# RasPiTimePowerSWv_1_5.net
KiCad netlist of a schematic drawn in EAGLE
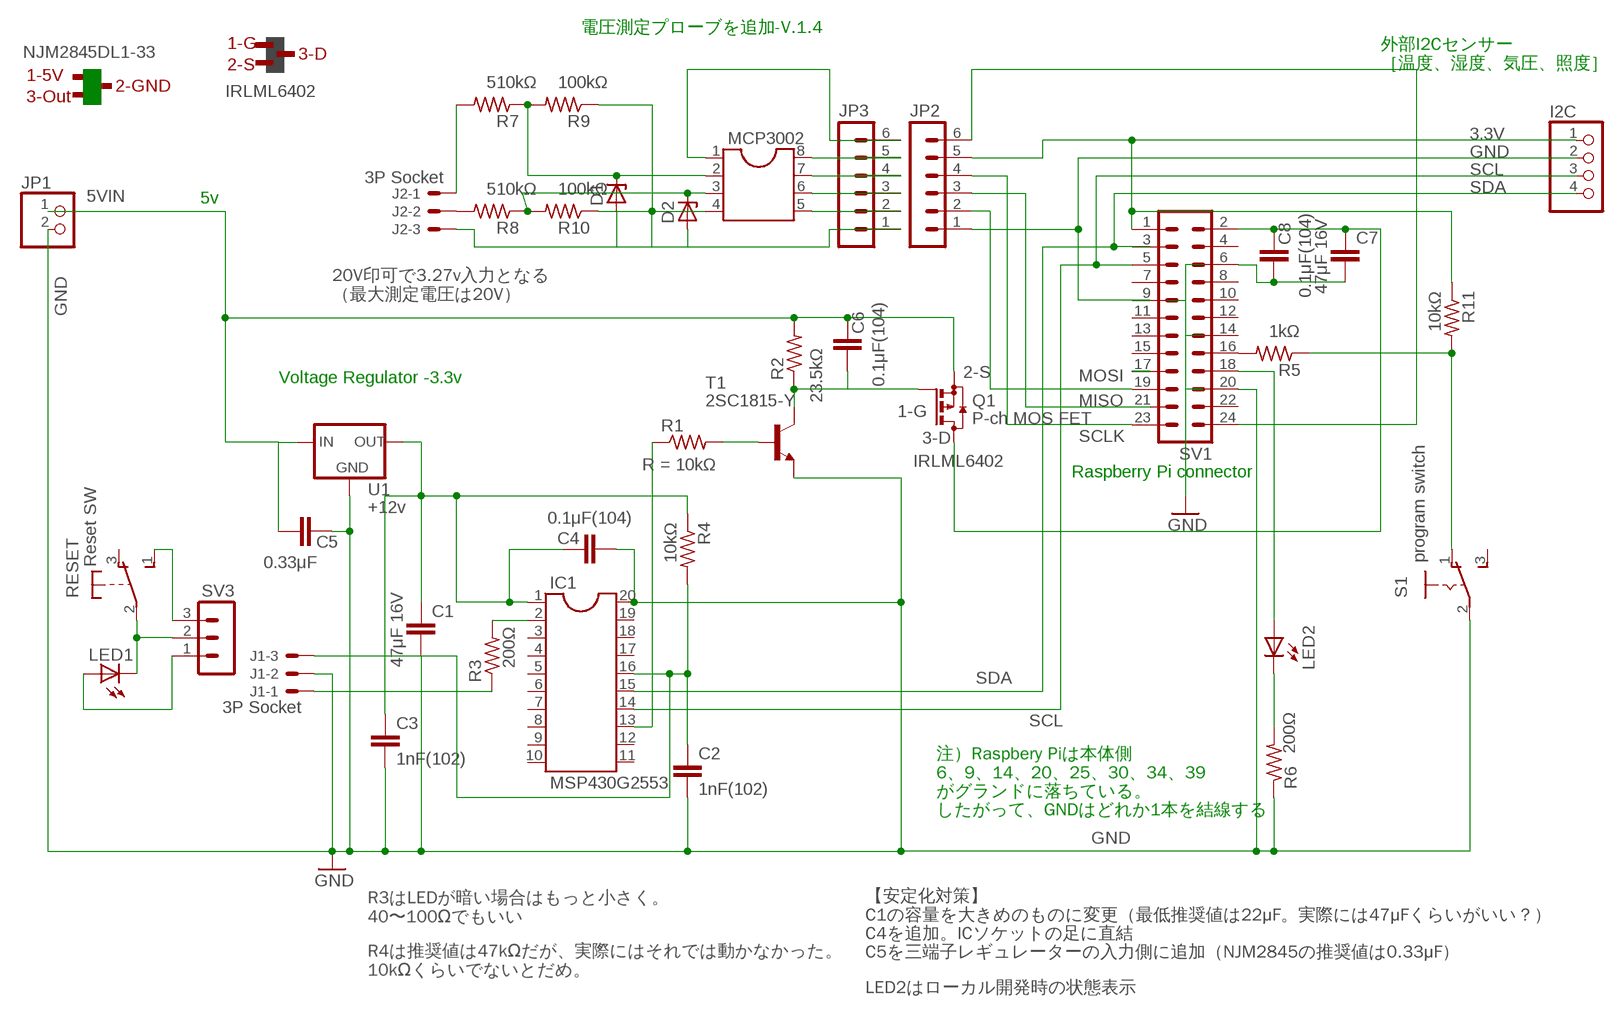
[diagram p0: schematic, sheet 1]

(export (version "E")
  (design (tool "Eeschema 10.0.6"))
  (components
    (comp (ref "C1")
      (value "47μF 16V")
      (footprint "eagle-import:C075-042X103")
      (libsource (lib "eagle-import") (part "C-EU075-042X103"))
    )
    (comp (ref "C2")
      (value "1nF(102)")
      (footprint "eagle-import:C025-024X044")
      (libsource (lib "eagle-import") (part "C-EU025-024X044"))
    )
    (comp (ref "C3")
      (value "1nF(102)")
      (footprint "eagle-import:C025-024X044")
      (libsource (lib "eagle-import") (part "C-EU025-024X044"))
    )
    (comp (ref "C4")
      (value "0.1μF(104)")
      (footprint "eagle-import:C025-024X044")
      (libsource (lib "eagle-import") (part "C-EU025-024X044"))
    )
    (comp (ref "C5")
      (value "0.33μF")
      (footprint "eagle-import:C025-024X044")
      (libsource (lib "eagle-import") (part "C-EU025-024X044"))
    )
    (comp (ref "C6")
      (value "0.1μF(104)")
      (footprint "eagle-import:C025-024X044")
      (libsource (lib "eagle-import") (part "C-EU025-024X044"))
    )
    (comp (ref "C7")
      (value "47μF 16V")
      (footprint "eagle-import:C075-042X103")
      (libsource (lib "eagle-import") (part "C-EU075-042X103"))
    )
    (comp (ref "C8")
      (value "0.1μF(104)")
      (footprint "eagle-import:C025-024X044")
      (libsource (lib "eagle-import") (part "C-EU025-024X044"))
    )
    (comp (ref "D1")
      (value "ZENER-DIODEDO34-7")
      (footprint "eagle-import:DO34Z7")
      (libsource (lib "eagle-import") (part "ZENER-DIODEDO34-7"))
    )
    (comp (ref "D2")
      (value "ZENER-DIODEDO34-7")
      (footprint "eagle-import:DO34Z7")
      (libsource (lib "eagle-import") (part "ZENER-DIODEDO34-7"))
    )
    (comp (ref "I2C")
      (value "PINHD-1X4")
      (footprint "eagle-import:1X04")
      (libsource (lib "eagle-import") (part "PINHD-1X4"))
    )
    (comp (ref "IC1")
      (value "MSP430G2553")
      (footprint "eagle-import:SOCKET-20")
      (libsource (lib "eagle-import") (part "DIL20S"))
    )
    (comp (ref "J1")
      (value "3P Socket")
      (footprint "eagle-import:6410-03")
      (libsource (lib "eagle-import") (part "22-?-0327-2031"))
    )
    (comp (ref "J2")
      (value "3P Socket")
      (footprint "eagle-import:6410-03")
      (libsource (lib "eagle-import") (part "22-?-0327-2031"))
    )
    (comp (ref "JP1")
      (value "PINHD-1X2")
      (footprint "eagle-import:1X02")
      (libsource (lib "eagle-import") (part "PINHD-1X2"))
    )
    (comp (ref "JP2")
      (value "MA06-1")
      (footprint "eagle-import:MA06-1")
      (libsource (lib "eagle-import") (part "MA06-1"))
    )
    (comp (ref "JP3")
      (value "MA06-1")
      (footprint "eagle-import:MA06-1")
      (libsource (lib "eagle-import") (part "MA06-1"))
    )
    (comp (ref "LED1")
      (value "TLLG4400")
      (footprint "eagle-import:LED3MM")
      (fields (field (name "MF") "VISHAY SEMICONDUCTOR"))
      (libsource (lib "eagle-import") (part "TLLG4400"))
    )
    (comp (ref "LED2")
      (value "TLLG4400")
      (footprint "eagle-import:LED3MM")
      (fields (field (name "MF") "VISHAY SEMICONDUCTOR"))
      (libsource (lib "eagle-import") (part "TLLG4400"))
    )
    (comp (ref "MCP3002")
      (value "DIL8")
      (footprint "eagle-import:DIL08")
      (libsource (lib "eagle-import") (part "DIL8"))
    )
    (comp (ref "Q1")
      (value "P-ch MOS FET")
      (footprint "eagle-import:SOT23")
      (libsource (lib "eagle-import") (part "BSS84"))
    )
    (comp (ref "R1")
      (value "R-US_MELF0102W")
      (footprint "eagle-import:MINI_MELF-0102W")
      (fields (field (name "R") "10kΩ"))
      (libsource (lib "eagle-import") (part "R-US_MELF0102W"))
    )
    (comp (ref "R2")
      (value "R-US_MELF0102W")
      (footprint "eagle-import:MINI_MELF-0102W")
      (fields (field (name "1K") "23.5kΩ"))
      (libsource (lib "eagle-import") (part "R-US_MELF0102W"))
    )
    (comp (ref "R3")
      (value "R-US_MELF0102W")
      (footprint "eagle-import:MINI_MELF-0102W")
      (fields (field (name "R") "200Ω"))
      (libsource (lib "eagle-import") (part "R-US_MELF0102W"))
    )
    (comp (ref "R4")
      (value "10kΩ")
      (footprint "eagle-import:MINI_MELF-0102W")
      (libsource (lib "eagle-import") (part "R-US_MELF0102W"))
    )
    (comp (ref "R5")
      (value "R-US_MELF0102W")
      (footprint "eagle-import:MINI_MELF-0102W")
      (fields (field (name "1K") "1kΩ"))
      (libsource (lib "eagle-import") (part "R-US_MELF0102W"))
    )
    (comp (ref "R6")
      (value "R-US_MELF0102W")
      (footprint "eagle-import:MINI_MELF-0102W")
      (fields (field (name "R") "200Ω"))
      (libsource (lib "eagle-import") (part "R-US_MELF0102W"))
    )
    (comp (ref "R7")
      (value "R-US_MELF0102W")
      (footprint "eagle-import:MINI_MELF-0102W")
      (fields (field (name "1K") "510kΩ"))
      (libsource (lib "eagle-import") (part "R-US_MELF0102W"))
    )
    (comp (ref "R8")
      (value "R-US_MELF0102W")
      (footprint "eagle-import:MINI_MELF-0102W")
      (fields (field (name "1K") "510kΩ"))
      (libsource (lib "eagle-import") (part "R-US_MELF0102W"))
    )
    (comp (ref "R9")
      (value "R-US_MELF0102W")
      (footprint "eagle-import:MINI_MELF-0102W")
      (fields (field (name "1K") "100kΩ"))
      (libsource (lib "eagle-import") (part "R-US_MELF0102W"))
    )
    (comp (ref "R10")
      (value "R-US_MELF0102W")
      (footprint "eagle-import:MINI_MELF-0102W")
      (fields (field (name "1K") "100kΩ"))
      (libsource (lib "eagle-import") (part "R-US_MELF0102W"))
    )
    (comp (ref "R11")
      (value "10kΩ")
      (footprint "eagle-import:MINI_MELF-0102W")
      (libsource (lib "eagle-import") (part "R-US_MELF0102W"))
    )
    (comp (ref "RESET")
      (value "Reset SW")
      (footprint "eagle-import:9450-1")
      (libsource (lib "eagle-import") (part "9450-1"))
    )
    (comp (ref "S1")
      (value "program switch")
      (footprint "eagle-import:255SB")
      (libsource (lib "eagle-import") (part "255SB"))
    )
    (comp (ref "SV1")
      (value "MA12-2")
      (footprint "eagle-import:MA12-2")
      (libsource (lib "eagle-import") (part "MA12-2"))
    )
    (comp (ref "SV3")
      (value "MA03-1")
      (footprint "eagle-import:MA03-1")
      (libsource (lib "eagle-import") (part "MA03-1"))
    )
    (comp (ref "T1")
      (value "2SC1815-Y")
      (footprint "eagle-import:TO92-ECB")
      (libsource (lib "eagle-import") (part "2SC1815"))
    )
    (comp (ref "U1")
      (value "+12v")
      (footprint "eagle-import:TO-252")
      (libsource (lib "eagle-import") (part "V_REG_78XX7812"))
    )
  )
  (nets
    (net (code "1") (name "/3.3V") (class "Default")
      (node (ref "C1") (pin "1") (pinfunction "1_1") (pintype "passive"))
      (node (ref "C3") (pin "1") (pinfunction "1_1") (pintype "passive"))
      (node (ref "C4") (pin "1") (pinfunction "1_1") (pintype "passive"))
      (node (ref "I2C") (pin "1") (pinfunction "1_1") (pintype "passive"))
      (node (ref "IC1") (pin "1") (pinfunction "1_1") (pintype "passive"))
      (node (ref "JP2") (pin "5") (pinfunction "5_5") (pintype "passive"))
      (node (ref "R11") (pin "1") (pinfunction "1_1") (pintype "passive"))
      (node (ref "R4") (pin "1") (pinfunction "1_1") (pintype "passive"))
      (node (ref "SV1") (pin "1") (pinfunction "1_1") (pintype "passive"))
      (node (ref "U1") (pin "2") (pinfunction "OUT_2") (pintype "passive"))
    )
    (net (code "2") (name "/5VIN") (class "Default")
      (node (ref "C5") (pin "2") (pinfunction "2_2") (pintype "passive"))
      (node (ref "C6") (pin "1") (pinfunction "1_1") (pintype "passive"))
      (node (ref "JP1") (pin "1") (pinfunction "1_1") (pintype "passive"))
      (node (ref "Q1") (pin "2") (pinfunction "S_2") (pintype "passive"))
      (node (ref "R2") (pin "2") (pinfunction "2_2") (pintype "passive"))
      (node (ref "U1") (pin "1") (pinfunction "IN_1") (pintype "input"))
    )
    (net (code "3") (name "/MISO") (class "Default")
      (node (ref "JP2") (pin "3") (pinfunction "3_3") (pintype "passive"))
      (node (ref "SV1") (pin "21") (pinfunction "21_21") (pintype "passive"))
    )
    (net (code "4") (name "/MOSI") (class "Default")
      (node (ref "JP2") (pin "2") (pinfunction "2_2") (pintype "passive"))
      (node (ref "SV1") (pin "19") (pinfunction "19_19") (pintype "passive"))
    )
    (net (code "5") (name "/SCL") (class "Default")
      (node (ref "I2C") (pin "3") (pinfunction "3_3") (pintype "passive"))
      (node (ref "IC1") (pin "14") (pinfunction "14_14") (pintype "passive"))
      (node (ref "SV1") (pin "5") (pinfunction "5_5") (pintype "passive"))
    )
    (net (code "6") (name "/SCLK") (class "Default")
      (node (ref "JP2") (pin "4") (pinfunction "4_4") (pintype "passive"))
      (node (ref "SV1") (pin "23") (pinfunction "23_23") (pintype "passive"))
    )
    (net (code "7") (name "/SDA") (class "Default")
      (node (ref "I2C") (pin "4") (pinfunction "4_4") (pintype "passive"))
      (node (ref "IC1") (pin "15") (pinfunction "15_15") (pintype "passive"))
      (node (ref "SV1") (pin "3") (pinfunction "3_3") (pintype "passive"))
    )
    (net (code "8") (name "GND") (class "Default")
      (node (ref "C1") (pin "2") (pinfunction "2_2") (pintype "passive"))
      (node (ref "C2") (pin "2") (pinfunction "2_2") (pintype "passive"))
      (node (ref "C3") (pin "2") (pinfunction "2_2") (pintype "passive"))
      (node (ref "C4") (pin "2") (pinfunction "2_2") (pintype "passive"))
      (node (ref "C5") (pin "1") (pinfunction "1_1") (pintype "passive"))
      (node (ref "I2C") (pin "2") (pinfunction "2_2") (pintype "passive"))
      (node (ref "IC1") (pin "20") (pinfunction "20_20") (pintype "passive"))
      (node (ref "J1") (pin "2") (pinfunction "S_2") (pintype "passive"))
      (node (ref "JP1") (pin "2") (pinfunction "2_2") (pintype "passive"))
      (node (ref "JP2") (pin "1") (pinfunction "1_1") (pintype "passive"))
      (node (ref "R6") (pin "1") (pinfunction "1_1") (pintype "passive"))
      (node (ref "S1") (pin "2") (pinfunction "P_2") (pintype "passive"))
      (node (ref "SV1") (pin "20") (pinfunction "20_20") (pintype "passive"))
      (node (ref "SV1") (pin "9") (pinfunction "9_9") (pintype "passive"))
      (node (ref "T1") (pin "E") (pinfunction "E_E") (pintype "passive"))
      (node (ref "U1") (pin "3") (pinfunction "GND_3") (pintype "input"))
    )
    (net (code "9") (name "Net-(C7-Pad2)") (class "Default")
      (node (ref "C7") (pin "2") (pinfunction "2_2") (pintype "passive"))
      (node (ref "C8") (pin "2") (pinfunction "2_2") (pintype "passive"))
      (node (ref "SV1") (pin "6") (pinfunction "6_6") (pintype "passive"))
    )
    (net (code "10") (name "Net-(D1-PadC)") (class "Default")
      (node (ref "D1") (pin "C") (pinfunction "C_C") (pintype "passive"))
      (node (ref "MCP3002") (pin "2") (pinfunction "2_2") (pintype "passive"))
      (node (ref "R7") (pin "1") (pinfunction "1_1") (pintype "passive"))
      (node (ref "R9") (pin "2") (pinfunction "2_2") (pintype "passive"))
    )
    (net (code "11") (name "Net-(D2-PadC)") (class "Default")
      (node (ref "D2") (pin "C") (pinfunction "C_C") (pintype "passive"))
      (node (ref "MCP3002") (pin "3") (pinfunction "3_3") (pintype "passive"))
      (node (ref "R10") (pin "2") (pinfunction "2_2") (pintype "passive"))
      (node (ref "R8") (pin "1") (pinfunction "1_1") (pintype "passive"))
    )
    (net (code "12") (name "Net-(IC1-Pad2)") (class "Default")
      (node (ref "IC1") (pin "2") (pinfunction "2_2") (pintype "passive"))
      (node (ref "R3") (pin "2") (pinfunction "2_2") (pintype "passive"))
    )
    (net (code "13") (name "Net-(IC1-Pad13)") (class "Default")
      (node (ref "IC1") (pin "13") (pinfunction "13_13") (pintype "passive"))
      (node (ref "R1") (pin "1") (pinfunction "1_1") (pintype "passive"))
    )
    (net (code "14") (name "Net-(J1A-S)") (class "Default")
      (node (ref "J1") (pin "1") (pinfunction "S_1") (pintype "passive"))
      (node (ref "R3") (pin "1") (pinfunction "1_1") (pintype "passive"))
    )
    (net (code "15") (name "Net-(J1C-S)") (class "Default")
      (node (ref "C2") (pin "1") (pinfunction "1_1") (pintype "passive"))
      (node (ref "IC1") (pin "16") (pinfunction "16_16") (pintype "passive"))
      (node (ref "J1") (pin "3") (pinfunction "S_3") (pintype "passive"))
      (node (ref "R4") (pin "2") (pinfunction "2_2") (pintype "passive"))
    )
    (net (code "16") (name "Net-(J2A-S)") (class "Default")
      (node (ref "J2") (pin "1") (pinfunction "S_1") (pintype "passive"))
      (node (ref "R7") (pin "2") (pinfunction "2_2") (pintype "passive"))
    )
    (net (code "17") (name "Net-(J2B-S)") (class "Default")
      (node (ref "J2") (pin "2") (pinfunction "S_2") (pintype "passive"))
      (node (ref "R8") (pin "2") (pinfunction "2_2") (pintype "passive"))
    )
    (net (code "18") (name "Net-(J2C-S)") (class "Default")
      (node (ref "D1") (pin "A") (pinfunction "A_A") (pintype "passive"))
      (node (ref "D2") (pin "A") (pinfunction "A_A") (pintype "passive"))
      (node (ref "J2") (pin "3") (pinfunction "S_3") (pintype "passive"))
      (node (ref "JP3") (pin "1") (pinfunction "1_1") (pintype "passive"))
      (node (ref "MCP3002") (pin "4") (pinfunction "4_4") (pintype "passive"))
      (node (ref "R10") (pin "1") (pinfunction "1_1") (pintype "passive"))
      (node (ref "R9") (pin "1") (pinfunction "1_1") (pintype "passive"))
    )
    (net (code "19") (name "Net-(JP2-Pad6)") (class "Default")
      (node (ref "JP2") (pin "6") (pinfunction "6_6") (pintype "passive"))
      (node (ref "SV1") (pin "24") (pinfunction "24_24") (pintype "passive"))
    )
    (net (code "20") (name "Net-(JP3-Pad2)") (class "Default")
      (node (ref "JP3") (pin "2") (pinfunction "2_2") (pintype "passive"))
      (node (ref "MCP3002") (pin "5") (pinfunction "5_5") (pintype "passive"))
    )
    (net (code "21") (name "Net-(JP3-Pad3)") (class "Default")
      (node (ref "JP3") (pin "3") (pinfunction "3_3") (pintype "passive"))
      (node (ref "MCP3002") (pin "6") (pinfunction "6_6") (pintype "passive"))
    )
    (net (code "22") (name "Net-(JP3-Pad4)") (class "Default")
      (node (ref "JP3") (pin "4") (pinfunction "4_4") (pintype "passive"))
      (node (ref "MCP3002") (pin "7") (pinfunction "7_7") (pintype "passive"))
    )
    (net (code "23") (name "Net-(JP3-Pad5)") (class "Default")
      (node (ref "JP3") (pin "5") (pinfunction "5_5") (pintype "passive"))
      (node (ref "MCP3002") (pin "8") (pinfunction "8_8") (pintype "passive"))
    )
    (net (code "24") (name "Net-(JP3-Pad6)") (class "Default")
      (node (ref "JP3") (pin "6") (pinfunction "6_6") (pintype "passive"))
      (node (ref "MCP3002") (pin "1") (pinfunction "1_1") (pintype "passive"))
    )
    (net (code "25") (name "Net-(LED1-C)") (class "Default")
      (node (ref "LED1") (pin "K") (pinfunction "C_K") (pintype "passive"))
      (node (ref "RESET") (pin "2") (pinfunction "P_2") (pintype "passive"))
      (node (ref "SV3") (pin "2") (pinfunction "2_2") (pintype "passive"))
    )
    (net (code "26") (name "Net-(LED1-PadA)") (class "Default")
      (node (ref "LED1") (pin "A") (pinfunction "A_A") (pintype "passive"))
      (node (ref "SV3") (pin "1") (pinfunction "1_1") (pintype "passive"))
    )
    (net (code "27") (name "Net-(LED2-C)") (class "Default")
      (node (ref "LED2") (pin "K") (pinfunction "C_K") (pintype "passive"))
      (node (ref "R6") (pin "2") (pinfunction "2_2") (pintype "passive"))
    )
    (net (code "28") (name "Net-(LED2-PadA)") (class "Default")
      (node (ref "LED2") (pin "A") (pinfunction "A_A") (pintype "passive"))
      (node (ref "SV1") (pin "18") (pinfunction "18_18") (pintype "passive"))
    )
    (net (code "29") (name "Net-(Q1-D)") (class "Default")
      (node (ref "C7") (pin "1") (pinfunction "1_1") (pintype "passive"))
      (node (ref "C8") (pin "1") (pinfunction "1_1") (pintype "passive"))
      (node (ref "Q1") (pin "3") (pinfunction "D_3") (pintype "passive"))
      (node (ref "SV1") (pin "2") (pinfunction "2_2") (pintype "passive"))
    )
    (net (code "30") (name "Net-(Q1-G)") (class "Default")
      (node (ref "C6") (pin "2") (pinfunction "2_2") (pintype "passive"))
      (node (ref "Q1") (pin "1") (pinfunction "G_1") (pintype "passive"))
      (node (ref "R2") (pin "1") (pinfunction "1_1") (pintype "passive"))
      (node (ref "T1") (pin "C") (pinfunction "C_C") (pintype "passive"))
    )
    (net (code "31") (name "Net-(R1-Pad2)") (class "Default")
      (node (ref "R1") (pin "2") (pinfunction "2_2") (pintype "passive"))
      (node (ref "T1") (pin "B") (pinfunction "B_B") (pintype "passive"))
    )
    (net (code "32") (name "Net-(R5-Pad2)") (class "Default")
      (node (ref "R5") (pin "2") (pinfunction "2_2") (pintype "passive"))
      (node (ref "SV1") (pin "16") (pinfunction "16_16") (pintype "passive"))
    )
    (net (code "33") (name "Net-(RESET-S)") (class "Default")
      (node (ref "RESET") (pin "1") (pinfunction "S_1") (pintype "passive"))
      (node (ref "SV3") (pin "3") (pinfunction "3_3") (pintype "passive"))
    )
    (net (code "34") (name "Net-(S1-O)") (class "Default")
      (node (ref "R11") (pin "2") (pinfunction "2_2") (pintype "passive"))
      (node (ref "R5") (pin "1") (pinfunction "1_1") (pintype "passive"))
      (node (ref "S1") (pin "1") (pinfunction "O_1") (pintype "passive"))
    )
    (net (code "35") (name "unconnected-(IC1-Pad3)") (class "Default")
      (node (ref "IC1") (pin "3") (pinfunction "3_3") (pintype "passive"))
    )
    (net (code "36") (name "unconnected-(IC1-Pad4)") (class "Default")
      (node (ref "IC1") (pin "4") (pinfunction "4_4") (pintype "passive"))
    )
    (net (code "37") (name "unconnected-(IC1-Pad5)") (class "Default")
      (node (ref "IC1") (pin "5") (pinfunction "5_5") (pintype "passive"))
    )
    (net (code "38") (name "unconnected-(IC1-Pad6)") (class "Default")
      (node (ref "IC1") (pin "6") (pinfunction "6_6") (pintype "passive"))
    )
    (net (code "39") (name "unconnected-(IC1-Pad7)") (class "Default")
      (node (ref "IC1") (pin "7") (pinfunction "7_7") (pintype "passive"))
    )
    (net (code "40") (name "unconnected-(IC1-Pad8)") (class "Default")
      (node (ref "IC1") (pin "8") (pinfunction "8_8") (pintype "passive"))
    )
    (net (code "41") (name "unconnected-(IC1-Pad9)") (class "Default")
      (node (ref "IC1") (pin "9") (pinfunction "9_9") (pintype "passive"))
    )
    (net (code "42") (name "unconnected-(IC1-Pad10)") (class "Default")
      (node (ref "IC1") (pin "10") (pinfunction "10_10") (pintype "passive"))
    )
    (net (code "43") (name "unconnected-(IC1-Pad11)") (class "Default")
      (node (ref "IC1") (pin "11") (pinfunction "11_11") (pintype "passive"))
    )
    (net (code "44") (name "unconnected-(IC1-Pad12)") (class "Default")
      (node (ref "IC1") (pin "12") (pinfunction "12_12") (pintype "passive"))
    )
    (net (code "45") (name "unconnected-(IC1-Pad17)") (class "Default")
      (node (ref "IC1") (pin "17") (pinfunction "17_17") (pintype "passive"))
    )
    (net (code "46") (name "unconnected-(IC1-Pad18)") (class "Default")
      (node (ref "IC1") (pin "18") (pinfunction "18_18") (pintype "passive"))
    )
    (net (code "47") (name "unconnected-(IC1-Pad19)") (class "Default")
      (node (ref "IC1") (pin "19") (pinfunction "19_19") (pintype "passive"))
    )
    (net (code "48") (name "unconnected-(RESET-O-Pad3)") (class "Default")
      (node (ref "RESET") (pin "3") (pinfunction "O_3") (pintype "passive"))
    )
    (net (code "49") (name "unconnected-(S1-S-Pad3)") (class "Default")
      (node (ref "S1") (pin "3") (pinfunction "S_3") (pintype "passive"))
    )
    (net (code "50") (name "unconnected-(SV1-Pad4)") (class "Default")
      (node (ref "SV1") (pin "4") (pinfunction "4_4") (pintype "passive"))
    )
    (net (code "51") (name "unconnected-(SV1-Pad7)") (class "Default")
      (node (ref "SV1") (pin "7") (pinfunction "7_7") (pintype "passive"))
    )
    (net (code "52") (name "unconnected-(SV1-Pad8)") (class "Default")
      (node (ref "SV1") (pin "8") (pinfunction "8_8") (pintype "passive"))
    )
    (net (code "53") (name "unconnected-(SV1-Pad10)") (class "Default")
      (node (ref "SV1") (pin "10") (pinfunction "10_10") (pintype "passive"))
    )
    (net (code "54") (name "unconnected-(SV1-Pad11)") (class "Default")
      (node (ref "SV1") (pin "11") (pinfunction "11_11") (pintype "passive"))
    )
    (net (code "55") (name "unconnected-(SV1-Pad12)") (class "Default")
      (node (ref "SV1") (pin "12") (pinfunction "12_12") (pintype "passive"))
    )
    (net (code "56") (name "unconnected-(SV1-Pad13)") (class "Default")
      (node (ref "SV1") (pin "13") (pinfunction "13_13") (pintype "passive"))
    )
    (net (code "57") (name "unconnected-(SV1-Pad14)") (class "Default")
      (node (ref "SV1") (pin "14") (pinfunction "14_14") (pintype "passive"))
    )
    (net (code "58") (name "unconnected-(SV1-Pad15)") (class "Default")
      (node (ref "SV1") (pin "15") (pinfunction "15_15") (pintype "passive"))
    )
    (net (code "59") (name "unconnected-(SV1-Pad17)") (class "Default")
      (node (ref "SV1") (pin "17") (pinfunction "17_17") (pintype "passive"))
    )
    (net (code "60") (name "unconnected-(SV1-Pad22)") (class "Default")
      (node (ref "SV1") (pin "22") (pinfunction "22_22") (pintype "passive"))
    )
  )
)
